# POWER.net
KiCad netlist of a schematic drawn in Altium Designer
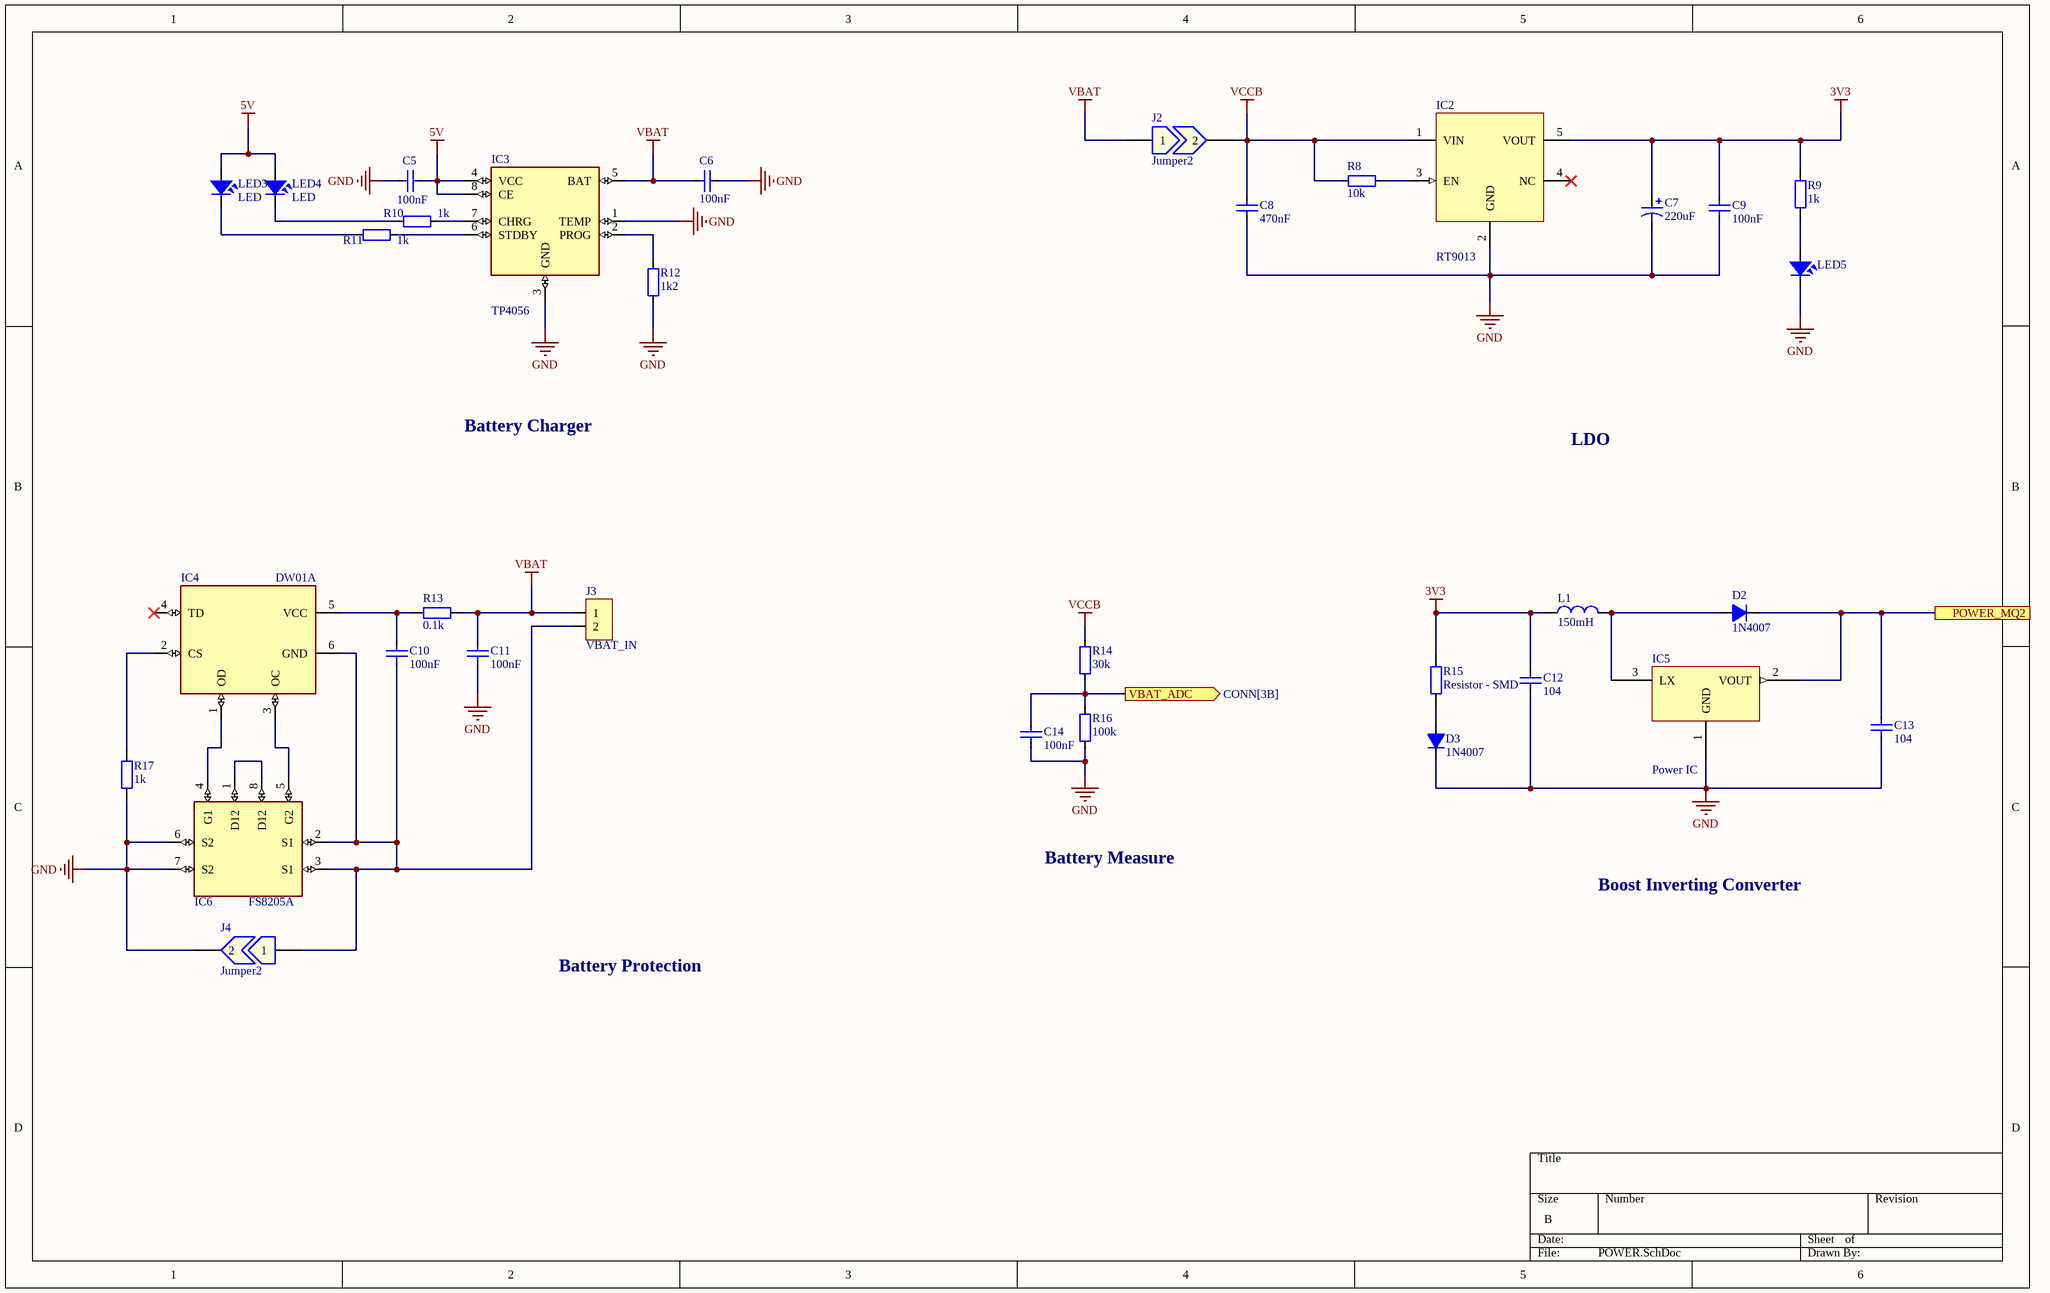
[diagram p0: POWER.SchDoc]

(export (version "E")
  (design (tool "Eeschema 10.0.6"))
  (components
    (comp (ref "C5")
      (value "100nF")
      (footprint "CAP_0805")
      (description "Capacitor")
      (fields (field (name "PUBLISHER") "Altium Limited"))
      (libsource (lib "My Library") (part "CapSMD"))
    )
    (comp (ref "C6")
      (value "100nF")
      (footprint "CAP_0805")
      (description "Capacitor")
      (fields (field (name "PUBLISHER") "Altium Limited"))
      (libsource (lib "My Library") (part "CapSMD"))
    )
    (comp (ref "C7")
      (value "220uF")
      (footprint "CAP_TANTALUM_3216")
      (description "Polarized Capacitor (Axial)")
      (fields (field (name "PUBLISHER") "Altium Limited"))
      (libsource (lib "My Library") (part "Cap Pol"))
    )
    (comp (ref "C8")
      (value "470nF")
      (footprint "CAP_0805")
      (description "Capacitor")
      (fields (field (name "PUBLISHER") "Altium Limited"))
      (libsource (lib "My Library") (part "CapSMD"))
    )
    (comp (ref "C9")
      (value "100nF")
      (footprint "CAP_0805")
      (description "Capacitor")
      (fields (field (name "PUBLISHER") "Altium Limited"))
      (libsource (lib "My Library") (part "CapSMD"))
    )
    (comp (ref "C10")
      (value "100nF")
      (footprint "CAP_0805")
      (description "Capacitor")
      (fields (field (name "PUBLISHER") "Altium Limited"))
      (libsource (lib "My Library") (part "CapSMD"))
    )
    (comp (ref "C11")
      (value "100nF")
      (footprint "CAP_0805")
      (description "Capacitor")
      (fields (field (name "PUBLISHER") "Altium Limited"))
      (libsource (lib "My Library") (part "CapSMD"))
    )
    (comp (ref "C12")
      (value "104")
      (footprint "CAP_0805")
      (description "Capacitor")
      (fields (field (name "PUBLISHER") "Altium Limited"))
      (libsource (lib "My Library") (part "CapSMD"))
    )
    (comp (ref "C13")
      (value "104")
      (footprint "CAP_0805")
      (description "Capacitor")
      (fields (field (name "PUBLISHER") "Altium Limited"))
      (libsource (lib "My Library") (part "CapSMD"))
    )
    (comp (ref "C14")
      (value "100nF")
      (footprint "CAP_0805")
      (description "Capacitor")
      (fields (field (name "PUBLISHER") "Altium Limited"))
      (libsource (lib "My Library") (part "CapSMD"))
    )
    (comp (ref "D2")
      (value "1N4007")
      (footprint "D1A")
      (description "Diode 1A")
      (libsource (lib "My Library") (part "D1A"))
    )
    (comp (ref "D3")
      (value "1N4007")
      (footprint "D1A")
      (description "Diode 1A")
      (libsource (lib "My Library") (part "D1A"))
    )
    (comp (ref "IC2")
      (value "RT9013")
      (footprint "SOT23-5")
      (description "https://linhkien.cxt.vn/5435-rt9013-33gb-ic-reg-linear-33v-500ma-sot23-5.html")
      (libsource (lib "My Library") (part "RT9013"))
    )
    (comp (ref "IC3")
      (value "TP4056")
      (footprint "TP4056")
      (description "Complete single cell Li-Ion battery with a constant current / constant voltage linear charger")
      (libsource (lib "My Library") (part "TP4056"))
    )
    (comp (ref "IC4")
      (value "DW01A")
      (footprint "SOT23-6")
      (description "One Cell Lithium-ion/Polymer Battery Protection IC")
      (libsource (lib "My Library") (part "DW01A"))
    )
    (comp (ref "IC5")
      (value "Power IC")
      (footprint "SOT-89-3")
      (description "Boost 5V IC 500mA")
      (libsource (lib "My Library") (part "CE8301A/BL8530"))
    )
    (comp (ref "IC6") (value "FS8205A") (footprint "FS8205A") (libsource (lib "My Library") (part "FS8205A")))
    (comp (ref "J2")
      (value "Jumper2")
      (footprint "JUMPER2")
      (description "Jumper, 2-Pin")
      (libsource (lib "Main") (part "Jumper2"))
    )
    (comp (ref "J3")
      (value "VBAT_IN")
      (footprint "JP2-D1T")
      (description "WR-PHD 2.54 mm Angled Socket Header")
      (fields
        (field (name "MANUFACTURER") "Würth Elektronik eiSos GmbH")
        (field (name "PARTNO") "613002143121")
        (field (name "CREATED BY") "Karrer Zheng")
      )
      (libsource (lib "My Library") (part "JP2"))
    )
    (comp (ref "J4")
      (value "Jumper2")
      (footprint "JUMPER2")
      (description "Jumper, 2-Pin")
      (libsource (lib "My Library") (part "Jumper2"))
    )
    (comp (ref "L1")
      (value "150mH")
      (footprint "L/0.4")
      (description "Inductor")
      (libsource (lib "My Library") (part "L1"))
    )
    (comp (ref "LED3")
      (value "LED")
      (footprint "LED-0805-Red")
      (description "LED Single colour Green and Red")
      (libsource (lib "My Library") (part "LED"))
    )
    (comp (ref "LED4")
      (value "LED")
      (footprint "LED-0805-Green")
      (description "LED Single colour Green and Red")
      (libsource (lib "My Library") (part "LED"))
    )
    (comp (ref "LED5")
      (value "~")
      (footprint "LED-0805-Red")
      (description "LED Single colour Green and Red")
      (libsource (lib "Main") (part "LED"))
    )
    (comp (ref "R8")
      (value "10k")
      (footprint "RES-SMD-0805")
      (description "Resistor")
      (fields
        (field (name "MANUFACTURER") "Generic Components")
        (field (name "PUBLISHER") "Altium Hobart Technology Centre")
      )
      (libsource (lib "My Library") (part "Resistor - SMD"))
    )
    (comp (ref "R9")
      (value "1k")
      (footprint "RES-SMD-0805")
      (description "Resistor SMD")
      (fields
        (field (name "MANUFACTURER") "Generic Components")
        (field (name "PUBLISHER") "Altium Hobart Technology Centre")
      )
      (libsource (lib "Main") (part "Resistor - SMD"))
    )
    (comp (ref "R10")
      (value "1k")
      (footprint "RES-SMD-0805")
      (description "Resistor")
      (fields
        (field (name "MANUFACTURER") "Generic Components")
        (field (name "PUBLISHER") "Altium Hobart Technology Centre")
      )
      (libsource (lib "My Library") (part "Resistor - SMD"))
    )
    (comp (ref "R11")
      (value "1k")
      (footprint "RES-SMD-0805")
      (description "Resistor")
      (fields
        (field (name "MANUFACTURER") "Generic Components")
        (field (name "PUBLISHER") "Altium Hobart Technology Centre")
      )
      (libsource (lib "My Library") (part "Resistor - SMD"))
    )
    (comp (ref "R12")
      (value "1k2")
      (footprint "RES-SMD-0805")
      (description "Resistor")
      (fields
        (field (name "MANUFACTURER") "Generic Components")
        (field (name "PUBLISHER") "Altium Hobart Technology Centre")
      )
      (libsource (lib "My Library") (part "Resistor - SMD"))
    )
    (comp (ref "R13")
      (value "0.1k")
      (footprint "RES-SMD-0805")
      (description "Resistor SMD")
      (fields
        (field (name "MANUFACTURER") "Generic Components")
        (field (name "PUBLISHER") "Altium Hobart Technology Centre")
      )
      (libsource (lib "") (part "Resistor - SMD_1"))
    )
    (comp (ref "R14")
      (value "30k")
      (footprint "RES-SMD-0805")
      (description "Resistor")
      (fields
        (field (name "MANUFACTURER") "Generic Components")
        (field (name "PUBLISHER") "Altium Hobart Technology Centre")
      )
      (libsource (lib "My Library") (part "Resistor - SMD"))
    )
    (comp (ref "R15")
      (value "Resistor - SMD")
      (footprint "RES-SMD-0805")
      (description "Resistor SMD")
      (fields
        (field (name "MANUFACTURER") "Generic Components")
        (field (name "PUBLISHER") "Altium Hobart Technology Centre")
      )
      (libsource (lib "") (part "Resistor - SMD_1"))
    )
    (comp (ref "R16")
      (value "100k")
      (footprint "RES-SMD-0805")
      (description "Resistor")
      (fields
        (field (name "MANUFACTURER") "Generic Components")
        (field (name "PUBLISHER") "Altium Hobart Technology Centre")
      )
      (libsource (lib "My Library") (part "Resistor - SMD"))
    )
    (comp (ref "R17")
      (value "1k")
      (footprint "RES-SMD-0805")
      (description "Resistor SMD")
      (fields
        (field (name "MANUFACTURER") "Generic Components")
        (field (name "PUBLISHER") "Altium Hobart Technology Centre")
      )
      (libsource (lib "") (part "Resistor - SMD_1"))
    )
  )
  (nets
    (net (code "1") (name "/POWER_MQ2") (class "Default")
      (node (ref "C13") (pin "2") (pinfunction "2_2") (pintype "passive"))
      (node (ref "D2") (pin "2") (pinfunction "K_2") (pintype "passive"))
      (node (ref "IC5") (pin "2") (pinfunction "VOUT_2") (pintype "output"))
    )
    (net (code "2") (name "/VBAT_ADC") (class "Default")
      (node (ref "C14") (pin "2") (pinfunction "2_2") (pintype "passive"))
      (node (ref "R14") (pin "2") (pinfunction "2_2") (pintype "passive"))
      (node (ref "R16") (pin "1") (pinfunction "1_1") (pintype "passive"))
    )
    (net (code "3") (name "3V3") (class "Default")
      (node (ref "C12") (pin "1") (pinfunction "1_1") (pintype "passive"))
      (node (ref "C7") (pin "1") (pinfunction "1_1") (pintype "passive"))
      (node (ref "C9") (pin "1") (pinfunction "1_1") (pintype "passive"))
      (node (ref "IC2") (pin "5") (pinfunction "VOUT_5") (pintype "power_in"))
      (node (ref "L1") (pin "1") (pinfunction "1_1") (pintype "passive"))
      (node (ref "R15") (pin "1") (pinfunction "1_1") (pintype "passive"))
      (node (ref "R9") (pin "2") (pinfunction "2_2") (pintype "passive"))
    )
    (net (code "4") (name "5V") (class "Default")
      (node (ref "C5") (pin "1") (pinfunction "1_1") (pintype "passive"))
      (node (ref "IC3") (pin "4") (pinfunction "VCC_4") (pintype "bidirectional"))
      (node (ref "IC3") (pin "8") (pinfunction "CE_8") (pintype "bidirectional"))
      (node (ref "LED3") (pin "1") (pinfunction "1_1") (pintype "passive"))
      (node (ref "LED4") (pin "1") (pinfunction "1_1") (pintype "passive"))
    )
    (net (code "5") (name "GND") (class "Default")
      (node (ref "C11") (pin "1") (pinfunction "1_1") (pintype "passive"))
      (node (ref "C12") (pin "2") (pinfunction "2_2") (pintype "passive"))
      (node (ref "C13") (pin "1") (pinfunction "1_1") (pintype "passive"))
      (node (ref "C14") (pin "1") (pinfunction "1_1") (pintype "passive"))
      (node (ref "C5") (pin "2") (pinfunction "2_2") (pintype "passive"))
      (node (ref "C6") (pin "1") (pinfunction "1_1") (pintype "passive"))
      (node (ref "C7") (pin "2") (pinfunction "2_2") (pintype "passive"))
      (node (ref "C8") (pin "2") (pinfunction "2_2") (pintype "passive"))
      (node (ref "C9") (pin "2") (pinfunction "2_2") (pintype "passive"))
      (node (ref "D3") (pin "2") (pinfunction "K_2") (pintype "passive"))
      (node (ref "IC2") (pin "2") (pinfunction "GND_2") (pintype "power_in"))
      (node (ref "IC3") (pin "1") (pinfunction "TEMP_1") (pintype "bidirectional"))
      (node (ref "IC3") (pin "3") (pinfunction "GND_3") (pintype "bidirectional"))
      (node (ref "IC5") (pin "1") (pinfunction "GND_1") (pintype "passive"))
      (node (ref "IC6") (pin "6") (pinfunction "S2_6") (pintype "bidirectional"))
      (node (ref "IC6") (pin "7") (pinfunction "S2_7") (pintype "bidirectional"))
      (node (ref "J4") (pin "2") (pinfunction "2_2") (pintype "passive"))
      (node (ref "LED5") (pin "2") (pinfunction "2_2") (pintype "passive"))
      (node (ref "R12") (pin "1") (pinfunction "1_1") (pintype "passive"))
      (node (ref "R16") (pin "2") (pinfunction "2_2") (pintype "passive"))
      (node (ref "R17") (pin "2") (pinfunction "2_2") (pintype "passive"))
    )
    (net (code "6") (name "Net-(D2-A)") (class "Default")
      (node (ref "D2") (pin "1") (pinfunction "A_1") (pintype "passive"))
      (node (ref "IC5") (pin "3") (pinfunction "LX_3") (pintype "passive"))
      (node (ref "L1") (pin "2") (pinfunction "2_2") (pintype "passive"))
    )
    (net (code "7") (name "Net-(D3-A)") (class "Default")
      (node (ref "D3") (pin "1") (pinfunction "A_1") (pintype "passive"))
      (node (ref "R15") (pin "2") (pinfunction "2_2") (pintype "passive"))
    )
    (net (code "8") (name "Net-(IC2-EN)") (class "Default")
      (node (ref "IC2") (pin "3") (pinfunction "EN_3") (pintype "input"))
      (node (ref "R8") (pin "1") (pinfunction "1_1") (pintype "passive"))
    )
    (net (code "9") (name "Net-(IC3-CHRG)") (class "Default")
      (node (ref "IC3") (pin "7") (pinfunction "CHRG_7") (pintype "bidirectional"))
      (node (ref "R10") (pin "1") (pinfunction "1_1") (pintype "passive"))
    )
    (net (code "10") (name "Net-(IC3-PROG)") (class "Default")
      (node (ref "IC3") (pin "2") (pinfunction "PROG_2") (pintype "bidirectional"))
      (node (ref "R12") (pin "2") (pinfunction "2_2") (pintype "passive"))
    )
    (net (code "11") (name "Net-(IC3-STDBY)") (class "Default")
      (node (ref "IC3") (pin "6") (pinfunction "STDBY_6") (pintype "bidirectional"))
      (node (ref "R11") (pin "1") (pinfunction "1_1") (pintype "passive"))
    )
    (net (code "12") (name "Net-(IC4-CS)") (class "Default")
      (node (ref "IC4") (pin "2") (pinfunction "CS_2") (pintype "bidirectional"))
      (node (ref "R17") (pin "1") (pinfunction "1_1") (pintype "passive"))
    )
    (net (code "13") (name "Net-(IC4-GND)") (class "Default")
      (node (ref "C10") (pin "1") (pinfunction "1_1") (pintype "passive"))
      (node (ref "IC4") (pin "6") (pinfunction "GND_6") (pintype "power_in"))
      (node (ref "IC6") (pin "2") (pinfunction "S1_2") (pintype "bidirectional"))
      (node (ref "IC6") (pin "3") (pinfunction "S1_3") (pintype "bidirectional"))
      (node (ref "J3") (pin "2") (pinfunction "2_2") (pintype "passive"))
      (node (ref "J4") (pin "1") (pinfunction "1_1") (pintype "passive"))
    )
    (net (code "14") (name "Net-(IC4-OC)") (class "Default")
      (node (ref "IC4") (pin "3") (pinfunction "OC_3") (pintype "bidirectional"))
      (node (ref "IC6") (pin "5") (pinfunction "G2_5") (pintype "bidirectional"))
    )
    (net (code "15") (name "Net-(IC4-OD)") (class "Default")
      (node (ref "IC4") (pin "1") (pinfunction "OD_1") (pintype "bidirectional"))
      (node (ref "IC6") (pin "4") (pinfunction "G1_4") (pintype "bidirectional"))
    )
    (net (code "16") (name "Net-(IC4-VCC)") (class "Default")
      (node (ref "C10") (pin "2") (pinfunction "2_2") (pintype "passive"))
      (node (ref "IC4") (pin "5") (pinfunction "VCC_5") (pintype "power_in"))
      (node (ref "R13") (pin "1") (pinfunction "1_1") (pintype "passive"))
    )
    (net (code "17") (name "Net-(IC6-D12-Pad1)") (class "Default")
      (node (ref "IC6") (pin "1") (pinfunction "D12_1") (pintype "bidirectional"))
      (node (ref "IC6") (pin "8") (pinfunction "D12_8") (pintype "bidirectional"))
    )
    (net (code "18") (name "Net-(LED3-Pad2)") (class "Default")
      (node (ref "LED3") (pin "2") (pinfunction "2_2") (pintype "passive"))
      (node (ref "R11") (pin "2") (pinfunction "2_2") (pintype "passive"))
    )
    (net (code "19") (name "Net-(LED4-Pad2)") (class "Default")
      (node (ref "LED4") (pin "2") (pinfunction "2_2") (pintype "passive"))
      (node (ref "R10") (pin "2") (pinfunction "2_2") (pintype "passive"))
    )
    (net (code "20") (name "Net-(LED5-Pad1)") (class "Default")
      (node (ref "LED5") (pin "1") (pinfunction "1_1") (pintype "passive"))
      (node (ref "R9") (pin "1") (pinfunction "1_1") (pintype "passive"))
    )
    (net (code "21") (name "VBAT") (class "Default")
      (node (ref "C11") (pin "2") (pinfunction "2_2") (pintype "passive"))
      (node (ref "C6") (pin "2") (pinfunction "2_2") (pintype "passive"))
      (node (ref "IC3") (pin "5") (pinfunction "BAT_5") (pintype "bidirectional"))
      (node (ref "J2") (pin "1") (pinfunction "1_1") (pintype "passive"))
      (node (ref "J3") (pin "1") (pinfunction "1_1") (pintype "passive"))
      (node (ref "R13") (pin "2") (pinfunction "2_2") (pintype "passive"))
    )
    (net (code "22") (name "VCCB") (class "Default")
      (node (ref "C8") (pin "1") (pinfunction "1_1") (pintype "passive"))
      (node (ref "IC2") (pin "1") (pinfunction "VIN_1") (pintype "power_in"))
      (node (ref "J2") (pin "2") (pinfunction "2_2") (pintype "passive"))
      (node (ref "R14") (pin "1") (pinfunction "1_1") (pintype "passive"))
      (node (ref "R8") (pin "2") (pinfunction "2_2") (pintype "passive"))
    )
    (net (code "23") (name "unconnected-(IC2-NC-Pad4)") (class "Default")
      (node (ref "IC2") (pin "4") (pinfunction "NC_4") (pintype "passive+no_connect"))
    )
    (net (code "24") (name "unconnected-(IC4-TD-Pad4)") (class "Default")
      (node (ref "IC4") (pin "4") (pinfunction "TD_4") (pintype "bidirectional+no_connect"))
    )
  )
)
